# Main.net
KiCad netlist of a schematic drawn in Altium Designer
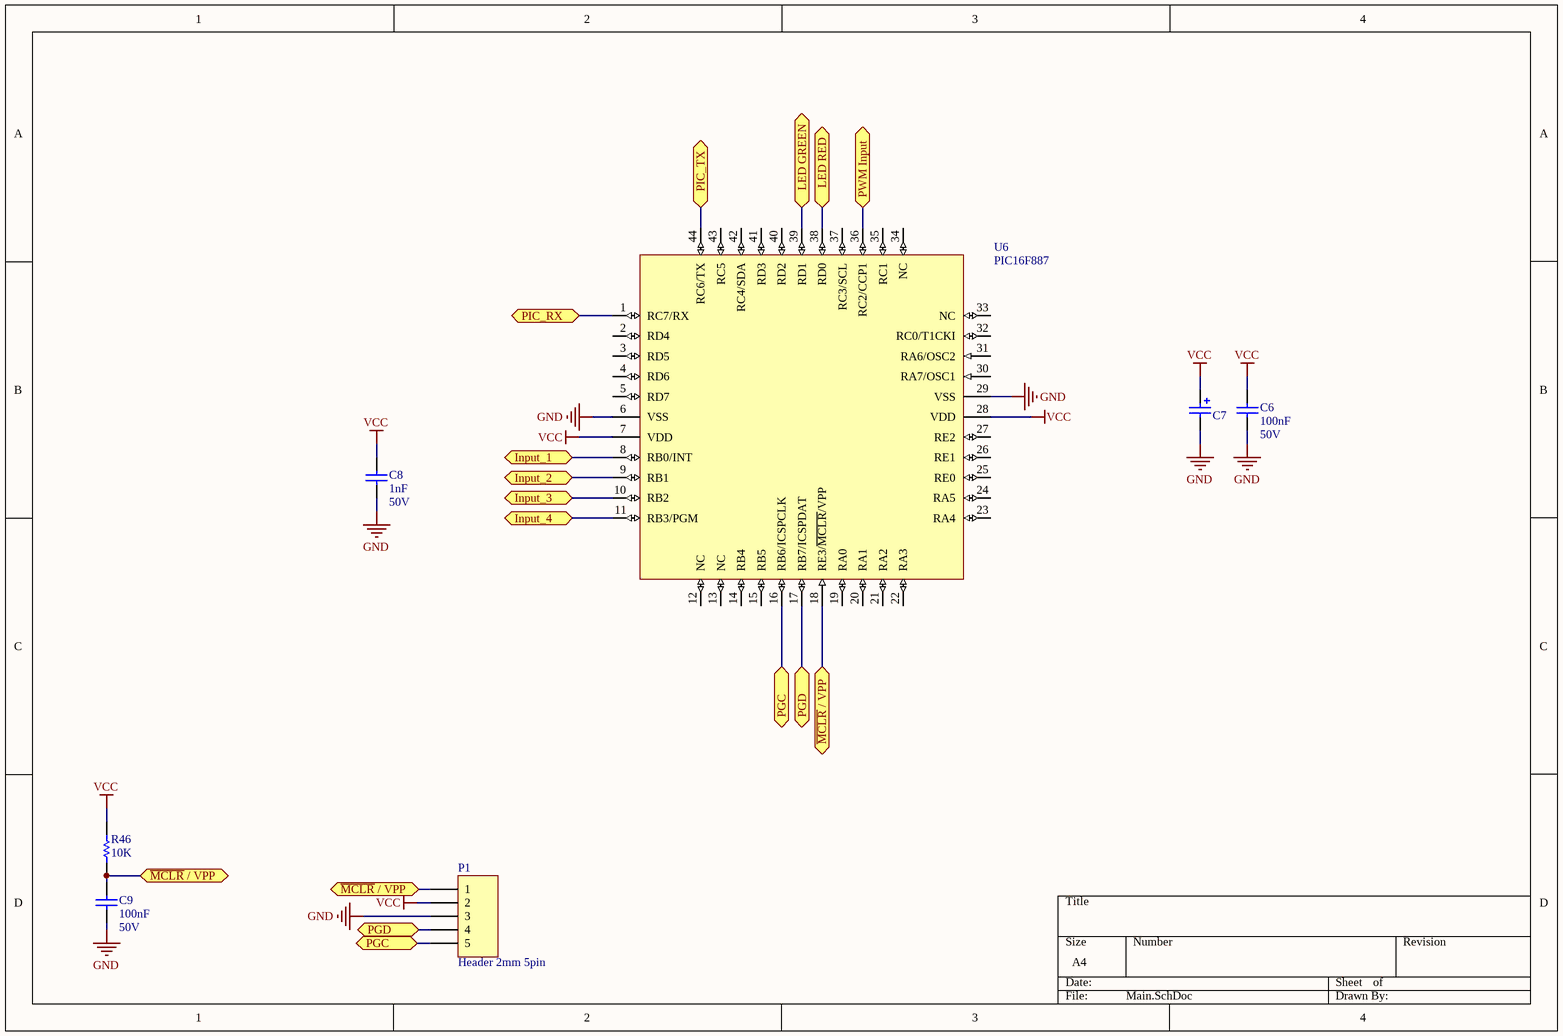
[diagram p0: Main.SchDoc]

(export (version "E")
  (design (tool "Eeschema 10.0.6"))
  (components
    (comp (ref "C6")
      (value "100nF")
      (footprint "3-0603_L")
      (description "Capacitor")
      (fields
        (field (name "VOLTAGE") "50V")
        (field (name "Comment") "Cap")
        (field (name "PUBLISHER") "Altium Limited")
      )
      (libsource (lib "Erdem_05112012") (part "Cap"))
    )
    (comp (ref "C7")
      (value "CAP-Tantal")
      (footprint "3528")
      (fields (field (name "VOLTAGE") "10V") (field (name "PUBLISHER") "Altium Limited"))
      (libsource (lib "Erdem_05112012") (part "CAP-Tantal"))
    )
    (comp (ref "C8")
      (value "1nF")
      (footprint "3-0603_L")
      (description "Capacitor")
      (fields
        (field (name "VOLTAGE") "50V")
        (field (name "Comment") "Cap")
        (field (name "PUBLISHER") "Altium Limited")
      )
      (libsource (lib "Erdem_05112012") (part "Cap"))
    )
    (comp (ref "C9")
      (value "100nF")
      (footprint "3-0603_L")
      (description "Capacitor")
      (fields
        (field (name "VOLTAGE") "50V")
        (field (name "Comment") "Cap")
        (field (name "PUBLISHER") "Altium Limited")
      )
      (libsource (lib "Erdem_05112012") (part "Cap"))
    )
    (comp (ref "P1")
      (value "Header 2mm 5pin")
      (footprint "Header 2mm 5Pin")
      (description "Header 2mm , 5-Pin")
      (fields (field (name "PUBLISHER") "Altium Limited"))
      (libsource (lib "Erdem_05112012") (part "Header 2mm 5pin"))
    )
    (comp (ref "R46")
      (value "10K")
      (footprint "3-0603_L")
      (description "Resistor")
      (fields (field (name "Comment") "Res1") (field (name "PUBLISHER") "Altium Limited"))
      (libsource (lib "Erdem_05112012") (part "Res1"))
    )
    (comp (ref "U6")
      (value "PIC16F887")
      (footprint "TQFP-44")
      (description "EPROM-Based 8-Bit CMOS Microcontroller")
      (fields (field (name "PUBLISHER") "Altium Limited"))
      (libsource (lib "Erdem_05112012") (part "PIC16F887"))
    )
  )
  (nets
    (net (code "1") (name "/Input_1") (class "Default")
      (node (ref "U6") (pin "8") (pinfunction "RB0/INT_8") (pintype "bidirectional"))
    )
    (net (code "2") (name "/Input_2") (class "Default")
      (node (ref "U6") (pin "9") (pinfunction "RB1_9") (pintype "bidirectional"))
    )
    (net (code "3") (name "/Input_3") (class "Default")
      (node (ref "U6") (pin "10") (pinfunction "RB2_10") (pintype "bidirectional"))
    )
    (net (code "4") (name "/Input_4") (class "Default")
      (node (ref "U6") (pin "11") (pinfunction "RB3/PGM_11") (pintype "bidirectional"))
    )
    (net (code "5") (name "/LED GREEN") (class "Default")
      (node (ref "U6") (pin "39") (pinfunction "RD1_39") (pintype "bidirectional"))
    )
    (net (code "6") (name "/LED RED") (class "Default")
      (node (ref "U6") (pin "38") (pinfunction "RD0_38") (pintype "bidirectional"))
    )
    (net (code "7") (name "/PGC") (class "Default")
      (node (ref "P1") (pin "5") (pinfunction "5_5") (pintype "passive"))
      (node (ref "U6") (pin "16") (pinfunction "RB6/ICSPCLK_16") (pintype "bidirectional"))
    )
    (net (code "8") (name "/PGD") (class "Default")
      (node (ref "P1") (pin "4") (pinfunction "4_4") (pintype "passive"))
      (node (ref "U6") (pin "17") (pinfunction "RB7/ICSPDAT_17") (pintype "bidirectional"))
    )
    (net (code "9") (name "/PIC_RX") (class "Default")
      (node (ref "U6") (pin "1") (pinfunction "RC7/RX_1") (pintype "bidirectional"))
    )
    (net (code "10") (name "/PIC_TX") (class "Default")
      (node (ref "U6") (pin "44") (pinfunction "RC6/TX_44") (pintype "bidirectional"))
    )
    (net (code "11") (name "/PWM Input") (class "Default")
      (node (ref "U6") (pin "36") (pinfunction "RC2/CCP1_36") (pintype "bidirectional"))
    )
    (net (code "12") (name "/~{MCLR} {slash} VPP") (class "Default")
      (node (ref "C9") (pin "1") (pinfunction "1_1") (pintype "passive"))
      (node (ref "P1") (pin "1") (pinfunction "1_1") (pintype "passive"))
      (node (ref "R46") (pin "1") (pinfunction "1_1") (pintype "passive"))
      (node (ref "U6") (pin "18") (pinfunction "RE3/~{MCLR}/VPP_18") (pintype "input"))
    )
    (net (code "13") (name "GND") (class "Default")
      (node (ref "C6") (pin "2") (pinfunction "2_2") (pintype "passive"))
      (node (ref "C7") (pin "2") (pinfunction "2_2") (pintype "passive"))
      (node (ref "C8") (pin "2") (pinfunction "2_2") (pintype "passive"))
      (node (ref "C9") (pin "2") (pinfunction "2_2") (pintype "passive"))
      (node (ref "P1") (pin "3") (pinfunction "3_3") (pintype "passive"))
      (node (ref "U6") (pin "29") (pinfunction "VSS_29") (pintype "power_in"))
      (node (ref "U6") (pin "6") (pinfunction "VSS_6") (pintype "power_in"))
    )
    (net (code "14") (name "VCC") (class "Default")
      (node (ref "C6") (pin "1") (pinfunction "1_1") (pintype "passive"))
      (node (ref "C7") (pin "1") (pinfunction "1_1") (pintype "passive"))
      (node (ref "C8") (pin "1") (pinfunction "1_1") (pintype "passive"))
      (node (ref "P1") (pin "2") (pinfunction "2_2") (pintype "passive"))
      (node (ref "R46") (pin "2") (pinfunction "2_2") (pintype "passive"))
      (node (ref "U6") (pin "28") (pinfunction "VDD_28") (pintype "power_in"))
      (node (ref "U6") (pin "7") (pinfunction "VDD_7") (pintype "power_in"))
    )
    (net (code "15") (name "unconnected-(U6-NC-Pad12)") (class "Default")
      (node (ref "U6") (pin "12") (pinfunction "NC_12") (pintype "bidirectional"))
    )
    (net (code "16") (name "unconnected-(U6-NC-Pad13)") (class "Default")
      (node (ref "U6") (pin "13") (pinfunction "NC_13") (pintype "bidirectional"))
    )
    (net (code "17") (name "unconnected-(U6-NC-Pad33)") (class "Default")
      (node (ref "U6") (pin "33") (pinfunction "NC_33") (pintype "bidirectional"))
    )
    (net (code "18") (name "unconnected-(U6-NC-Pad34)") (class "Default")
      (node (ref "U6") (pin "34") (pinfunction "NC_34") (pintype "bidirectional"))
    )
    (net (code "19") (name "unconnected-(U6-RA0-Pad19)") (class "Default")
      (node (ref "U6") (pin "19") (pinfunction "RA0_19") (pintype "bidirectional"))
    )
    (net (code "20") (name "unconnected-(U6-RA1-Pad20)") (class "Default")
      (node (ref "U6") (pin "20") (pinfunction "RA1_20") (pintype "bidirectional"))
    )
    (net (code "21") (name "unconnected-(U6-RA2-Pad21)") (class "Default")
      (node (ref "U6") (pin "21") (pinfunction "RA2_21") (pintype "bidirectional"))
    )
    (net (code "22") (name "unconnected-(U6-RA3-Pad22)") (class "Default")
      (node (ref "U6") (pin "22") (pinfunction "RA3_22") (pintype "bidirectional"))
    )
    (net (code "23") (name "unconnected-(U6-RA4-Pad23)") (class "Default")
      (node (ref "U6") (pin "23") (pinfunction "RA4_23") (pintype "bidirectional"))
    )
    (net (code "24") (name "unconnected-(U6-RA5-Pad24)") (class "Default")
      (node (ref "U6") (pin "24") (pinfunction "RA5_24") (pintype "bidirectional"))
    )
    (net (code "25") (name "unconnected-(U6-RA6{slash}OSC2-Pad31)") (class "Default")
      (node (ref "U6") (pin "31") (pinfunction "RA6/OSC2_31") (pintype "input"))
    )
    (net (code "26") (name "unconnected-(U6-RA7{slash}OSC1-Pad30)") (class "Default")
      (node (ref "U6") (pin "30") (pinfunction "RA7/OSC1_30") (pintype "input"))
    )
    (net (code "27") (name "unconnected-(U6-RB4-Pad14)") (class "Default")
      (node (ref "U6") (pin "14") (pinfunction "RB4_14") (pintype "bidirectional"))
    )
    (net (code "28") (name "unconnected-(U6-RB5-Pad15)") (class "Default")
      (node (ref "U6") (pin "15") (pinfunction "RB5_15") (pintype "bidirectional"))
    )
    (net (code "29") (name "unconnected-(U6-RC0{slash}T1CKI-Pad32)") (class "Default")
      (node (ref "U6") (pin "32") (pinfunction "RC0/T1CKI_32") (pintype "bidirectional"))
    )
    (net (code "30") (name "unconnected-(U6-RC1-Pad35)") (class "Default")
      (node (ref "U6") (pin "35") (pinfunction "RC1_35") (pintype "bidirectional"))
    )
    (net (code "31") (name "unconnected-(U6-RC3{slash}SCL-Pad37)") (class "Default")
      (node (ref "U6") (pin "37") (pinfunction "RC3/SCL_37") (pintype "bidirectional"))
    )
    (net (code "32") (name "unconnected-(U6-RC4{slash}SDA-Pad42)") (class "Default")
      (node (ref "U6") (pin "42") (pinfunction "RC4/SDA_42") (pintype "bidirectional"))
    )
    (net (code "33") (name "unconnected-(U6-RC5-Pad43)") (class "Default")
      (node (ref "U6") (pin "43") (pinfunction "RC5_43") (pintype "bidirectional"))
    )
    (net (code "34") (name "unconnected-(U6-RD2-Pad40)") (class "Default")
      (node (ref "U6") (pin "40") (pinfunction "RD2_40") (pintype "bidirectional"))
    )
    (net (code "35") (name "unconnected-(U6-RD3-Pad41)") (class "Default")
      (node (ref "U6") (pin "41") (pinfunction "RD3_41") (pintype "bidirectional"))
    )
    (net (code "36") (name "unconnected-(U6-RD4-Pad2)") (class "Default")
      (node (ref "U6") (pin "2") (pinfunction "RD4_2") (pintype "bidirectional"))
    )
    (net (code "37") (name "unconnected-(U6-RD5-Pad3)") (class "Default")
      (node (ref "U6") (pin "3") (pinfunction "RD5_3") (pintype "bidirectional"))
    )
    (net (code "38") (name "unconnected-(U6-RD6-Pad4)") (class "Default")
      (node (ref "U6") (pin "4") (pinfunction "RD6_4") (pintype "bidirectional"))
    )
    (net (code "39") (name "unconnected-(U6-RD7-Pad5)") (class "Default")
      (node (ref "U6") (pin "5") (pinfunction "RD7_5") (pintype "bidirectional"))
    )
    (net (code "40") (name "unconnected-(U6-RE0-Pad25)") (class "Default")
      (node (ref "U6") (pin "25") (pinfunction "RE0_25") (pintype "bidirectional"))
    )
    (net (code "41") (name "unconnected-(U6-RE1-Pad26)") (class "Default")
      (node (ref "U6") (pin "26") (pinfunction "RE1_26") (pintype "bidirectional"))
    )
    (net (code "42") (name "unconnected-(U6-RE2-Pad27)") (class "Default")
      (node (ref "U6") (pin "27") (pinfunction "RE2_27") (pintype "bidirectional"))
    )
  )
)
